# M606X.net
KiCad netlist of a schematic drawn in EAGLE
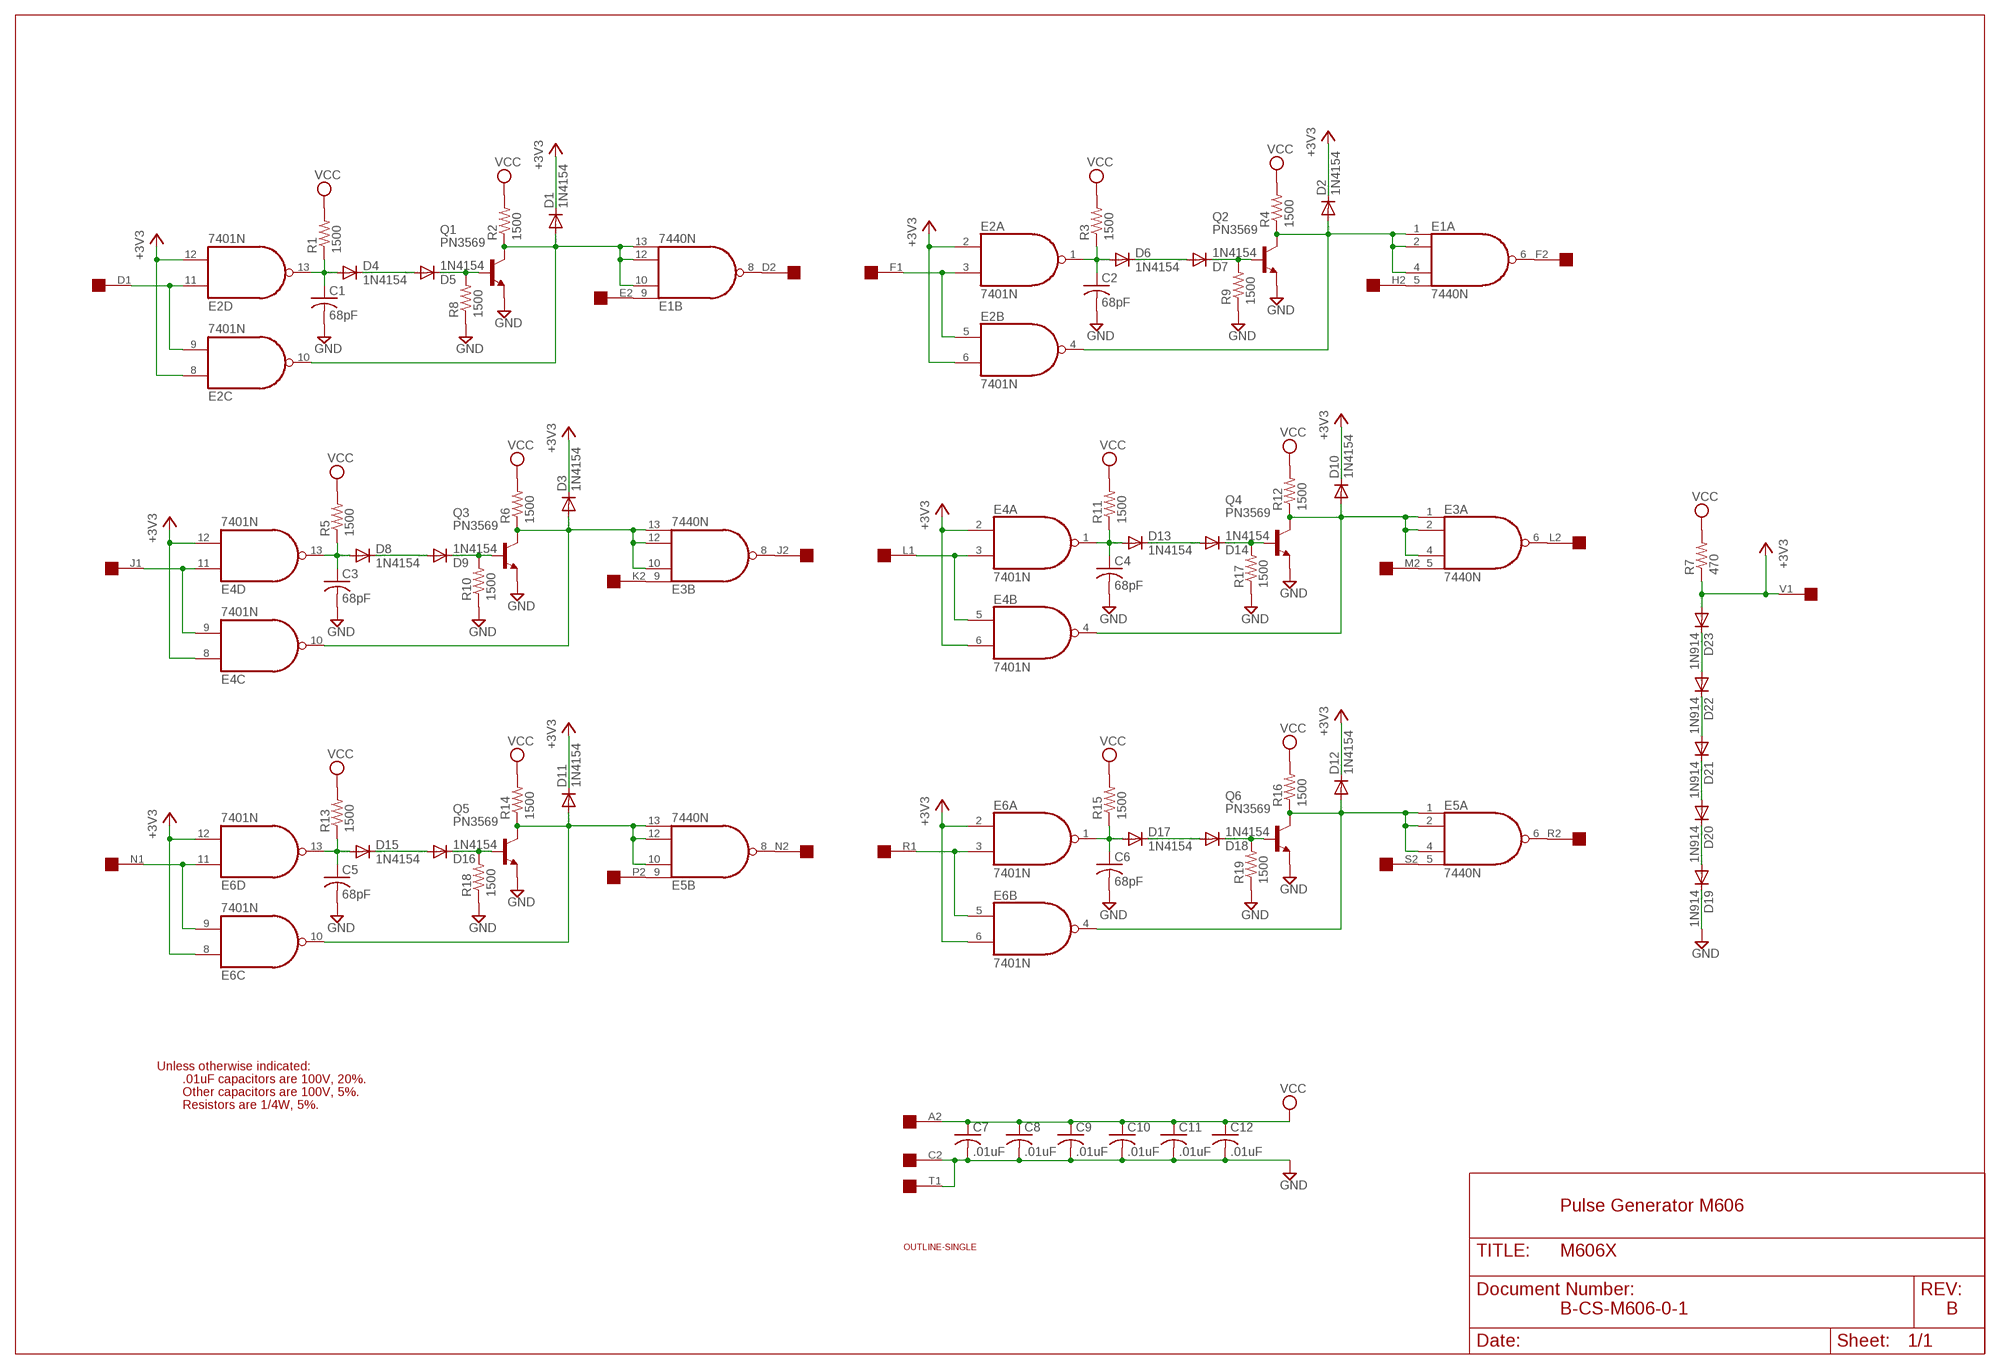
[diagram p0: schematic, sheet 1]

(export (version "E")
  (design (tool "Eeschema 10.0.6"))
  (components
    (comp (ref "C1")
      (value "68pF")
      (footprint "eagle-import:C075-032X103")
      (libsource (lib "eagle-import") (part "C-US075-032X103"))
    )
    (comp (ref "C2")
      (value "68pF")
      (footprint "eagle-import:C075-032X103")
      (libsource (lib "eagle-import") (part "C-US075-032X103"))
    )
    (comp (ref "C3")
      (value "68pF")
      (footprint "eagle-import:C075-032X103")
      (libsource (lib "eagle-import") (part "C-US075-032X103"))
    )
    (comp (ref "C4")
      (value "68pF")
      (footprint "eagle-import:C075-032X103")
      (libsource (lib "eagle-import") (part "C-US075-032X103"))
    )
    (comp (ref "C5")
      (value "68pF")
      (footprint "eagle-import:C075-032X103")
      (libsource (lib "eagle-import") (part "C-US075-032X103"))
    )
    (comp (ref "C6")
      (value "68pF")
      (footprint "eagle-import:C075-032X103")
      (libsource (lib "eagle-import") (part "C-US075-032X103"))
    )
    (comp (ref "C7")
      (value ".01uF")
      (footprint "eagle-import:C050-025X075")
      (libsource (lib "eagle-import") (part "C-US050-025X075"))
    )
    (comp (ref "C8")
      (value ".01uF")
      (footprint "eagle-import:C050-025X075")
      (libsource (lib "eagle-import") (part "C-US050-025X075"))
    )
    (comp (ref "C9")
      (value ".01uF")
      (footprint "eagle-import:C050-025X075")
      (libsource (lib "eagle-import") (part "C-US050-025X075"))
    )
    (comp (ref "C10")
      (value ".01uF")
      (footprint "eagle-import:C050-025X075")
      (libsource (lib "eagle-import") (part "C-US050-025X075"))
    )
    (comp (ref "C11")
      (value ".01uF")
      (footprint "eagle-import:C050-025X075")
      (libsource (lib "eagle-import") (part "C-US050-025X075"))
    )
    (comp (ref "C12")
      (value ".01uF")
      (footprint "eagle-import:C050-025X075")
      (libsource (lib "eagle-import") (part "C-US050-025X075"))
    )
    (comp (ref "D1")
      (value "1N4154")
      (footprint "eagle-import:DO35-10")
      (libsource (lib "eagle-import") (part "1N4148DO35-10"))
    )
    (comp (ref "D2")
      (value "1N4154")
      (footprint "eagle-import:DO35-10")
      (libsource (lib "eagle-import") (part "1N4148DO35-10"))
    )
    (comp (ref "D3")
      (value "1N4154")
      (footprint "eagle-import:DO35-10")
      (libsource (lib "eagle-import") (part "1N4148DO35-10"))
    )
    (comp (ref "D4")
      (value "1N4154")
      (footprint "eagle-import:DO35-10")
      (libsource (lib "eagle-import") (part "1N4148DO35-10"))
    )
    (comp (ref "D5")
      (value "1N4154")
      (footprint "eagle-import:DO35-10")
      (libsource (lib "eagle-import") (part "1N4148DO35-10"))
    )
    (comp (ref "D6")
      (value "1N4154")
      (footprint "eagle-import:DO35-10")
      (libsource (lib "eagle-import") (part "1N4148DO35-10"))
    )
    (comp (ref "D7")
      (value "1N4154")
      (footprint "eagle-import:DO35-10")
      (libsource (lib "eagle-import") (part "1N4148DO35-10"))
    )
    (comp (ref "D8")
      (value "1N4154")
      (footprint "eagle-import:DO35-10")
      (libsource (lib "eagle-import") (part "1N4148DO35-10"))
    )
    (comp (ref "D9")
      (value "1N4154")
      (footprint "eagle-import:DO35-10")
      (libsource (lib "eagle-import") (part "1N4148DO35-10"))
    )
    (comp (ref "D10")
      (value "1N4154")
      (footprint "eagle-import:DO35-10")
      (libsource (lib "eagle-import") (part "1N4148DO35-10"))
    )
    (comp (ref "D11")
      (value "1N4154")
      (footprint "eagle-import:DO35-10")
      (libsource (lib "eagle-import") (part "1N4148DO35-10"))
    )
    (comp (ref "D12")
      (value "1N4154")
      (footprint "eagle-import:DO35-10")
      (libsource (lib "eagle-import") (part "1N4148DO35-10"))
    )
    (comp (ref "D13")
      (value "1N4154")
      (footprint "eagle-import:DO35-10")
      (libsource (lib "eagle-import") (part "1N4148DO35-10"))
    )
    (comp (ref "D14")
      (value "1N4154")
      (footprint "eagle-import:DO35-10")
      (libsource (lib "eagle-import") (part "1N4148DO35-10"))
    )
    (comp (ref "D15")
      (value "1N4154")
      (footprint "eagle-import:DO35-10")
      (libsource (lib "eagle-import") (part "1N4148DO35-10"))
    )
    (comp (ref "D16")
      (value "1N4154")
      (footprint "eagle-import:DO35-10")
      (libsource (lib "eagle-import") (part "1N4148DO35-10"))
    )
    (comp (ref "D17")
      (value "1N4154")
      (footprint "eagle-import:DO35-10")
      (libsource (lib "eagle-import") (part "1N4148DO35-10"))
    )
    (comp (ref "D18")
      (value "1N4154")
      (footprint "eagle-import:DO35-10")
      (libsource (lib "eagle-import") (part "1N4148DO35-10"))
    )
    (comp (ref "D19")
      (value "1N914")
      (footprint "eagle-import:DO35-10")
      (libsource (lib "eagle-import") (part "1N4148DO35-10"))
    )
    (comp (ref "D20")
      (value "1N914")
      (footprint "eagle-import:DO35-10")
      (libsource (lib "eagle-import") (part "1N4148DO35-10"))
    )
    (comp (ref "D21")
      (value "1N914")
      (footprint "eagle-import:DO35-10")
      (libsource (lib "eagle-import") (part "1N4148DO35-10"))
    )
    (comp (ref "D22")
      (value "1N914")
      (footprint "eagle-import:DO35-10")
      (libsource (lib "eagle-import") (part "1N4148DO35-10"))
    )
    (comp (ref "D23")
      (value "1N914")
      (footprint "eagle-import:DO35-10")
      (libsource (lib "eagle-import") (part "1N4148DO35-10"))
    )
    (comp (ref "E1")
      (value "7440N")
      (footprint "eagle-import:DIL14")
      (libsource (lib "eagle-import") (part "7420NS"))
    )
    (comp (ref "E2")
      (value "7401N")
      (footprint "eagle-import:DIL14")
      (libsource (lib "eagle-import") (part "7401NLS"))
    )
    (comp (ref "E3")
      (value "7440N")
      (footprint "eagle-import:DIL14")
      (libsource (lib "eagle-import") (part "7420NS"))
    )
    (comp (ref "E4")
      (value "7401N")
      (footprint "eagle-import:DIL14")
      (libsource (lib "eagle-import") (part "7401NLS"))
    )
    (comp (ref "E5")
      (value "7440N")
      (footprint "eagle-import:DIL14")
      (libsource (lib "eagle-import") (part "7420NS"))
    )
    (comp (ref "E6")
      (value "7401N")
      (footprint "eagle-import:DIL14")
      (libsource (lib "eagle-import") (part "7401NLS"))
    )
    (comp (ref "Q1")
      (value "PN3569")
      (footprint "eagle-import:TO39")
      (libsource (lib "eagle-import") (part "2N3019"))
    )
    (comp (ref "Q2")
      (value "PN3569")
      (footprint "eagle-import:TO39")
      (libsource (lib "eagle-import") (part "2N3019"))
    )
    (comp (ref "Q3")
      (value "PN3569")
      (footprint "eagle-import:TO39")
      (libsource (lib "eagle-import") (part "2N3019"))
    )
    (comp (ref "Q4")
      (value "PN3569")
      (footprint "eagle-import:TO39")
      (libsource (lib "eagle-import") (part "2N3019"))
    )
    (comp (ref "Q5")
      (value "PN3569")
      (footprint "eagle-import:TO39")
      (libsource (lib "eagle-import") (part "2N3019"))
    )
    (comp (ref "Q6")
      (value "PN3569")
      (footprint "eagle-import:TO39")
      (libsource (lib "eagle-import") (part "2N3019"))
    )
    (comp (ref "R1")
      (value "1500")
      (footprint "eagle-import:0207_10")
      (libsource (lib "eagle-import") (part "R-US_0207/10"))
    )
    (comp (ref "R2")
      (value "1500")
      (footprint "eagle-import:0207_10")
      (libsource (lib "eagle-import") (part "R-US_0207/10"))
    )
    (comp (ref "R3")
      (value "1500")
      (footprint "eagle-import:0207_10")
      (libsource (lib "eagle-import") (part "R-US_0207/10"))
    )
    (comp (ref "R4")
      (value "1500")
      (footprint "eagle-import:0207_10")
      (libsource (lib "eagle-import") (part "R-US_0207/10"))
    )
    (comp (ref "R5")
      (value "1500")
      (footprint "eagle-import:0207_10")
      (libsource (lib "eagle-import") (part "R-US_0207/10"))
    )
    (comp (ref "R6")
      (value "1500")
      (footprint "eagle-import:0207_10")
      (libsource (lib "eagle-import") (part "R-US_0207/10"))
    )
    (comp (ref "R7")
      (value "470")
      (footprint "eagle-import:0207_10")
      (libsource (lib "eagle-import") (part "R-US_0207/10"))
    )
    (comp (ref "R8")
      (value "1500")
      (footprint "eagle-import:0207_10")
      (libsource (lib "eagle-import") (part "R-US_0207/10"))
    )
    (comp (ref "R9")
      (value "1500")
      (footprint "eagle-import:0207_10")
      (libsource (lib "eagle-import") (part "R-US_0207/10"))
    )
    (comp (ref "R10")
      (value "1500")
      (footprint "eagle-import:0207_10")
      (libsource (lib "eagle-import") (part "R-US_0207/10"))
    )
    (comp (ref "R11")
      (value "1500")
      (footprint "eagle-import:0207_10")
      (libsource (lib "eagle-import") (part "R-US_0207/10"))
    )
    (comp (ref "R12")
      (value "1500")
      (footprint "eagle-import:0207_10")
      (libsource (lib "eagle-import") (part "R-US_0207/10"))
    )
    (comp (ref "R13")
      (value "1500")
      (footprint "eagle-import:0207_10")
      (libsource (lib "eagle-import") (part "R-US_0207/10"))
    )
    (comp (ref "R14")
      (value "1500")
      (footprint "eagle-import:0207_10")
      (libsource (lib "eagle-import") (part "R-US_0207/10"))
    )
    (comp (ref "R15")
      (value "1500")
      (footprint "eagle-import:0207_10")
      (libsource (lib "eagle-import") (part "R-US_0207/10"))
    )
    (comp (ref "R16")
      (value "1500")
      (footprint "eagle-import:0207_10")
      (libsource (lib "eagle-import") (part "R-US_0207/10"))
    )
    (comp (ref "R17")
      (value "1500")
      (footprint "eagle-import:0207_10")
      (libsource (lib "eagle-import") (part "R-US_0207/10"))
    )
    (comp (ref "R18")
      (value "1500")
      (footprint "eagle-import:0207_10")
      (libsource (lib "eagle-import") (part "R-US_0207/10"))
    )
    (comp (ref "R19")
      (value "1500")
      (footprint "eagle-import:0207_10")
      (libsource (lib "eagle-import") (part "R-US_0207/10"))
    )
    (comp (ref "U$2")
      (value "SINGLE")
      (footprint "eagle-import:EDGE-CON2")
      (libsource (lib "eagle-import") (part "SINGLE"))
    )
    (comp (ref "U$4")
      (value "OUTLINE-SINGLE")
      (footprint "eagle-import:SINGLE")
      (libsource (lib "eagle-import") (part "OUTLINE-SINGLE"))
    )
  )
  (nets
    (net (code "1") (name "+3V3") (class "Default")
      (node (ref "D1") (pin "C") (pinfunction "C_C") (pintype "passive"))
      (node (ref "D10") (pin "C") (pinfunction "C_C") (pintype "passive"))
      (node (ref "D11") (pin "C") (pinfunction "C_C") (pintype "passive"))
      (node (ref "D12") (pin "C") (pinfunction "C_C") (pintype "passive"))
      (node (ref "D2") (pin "C") (pinfunction "C_C") (pintype "passive"))
      (node (ref "D23") (pin "A") (pinfunction "A_A") (pintype "passive"))
      (node (ref "D3") (pin "C") (pinfunction "C_C") (pintype "passive"))
      (node (ref "E2") (pin "12") (pinfunction "I1_12") (pintype "input"))
      (node (ref "E2") (pin "2") (pinfunction "I0_2") (pintype "input"))
      (node (ref "E2") (pin "6") (pinfunction "I1_6") (pintype "input"))
      (node (ref "E2") (pin "8") (pinfunction "I0_8") (pintype "input"))
      (node (ref "E4") (pin "12") (pinfunction "I1_12") (pintype "input"))
      (node (ref "E4") (pin "2") (pinfunction "I0_2") (pintype "input"))
      (node (ref "E4") (pin "6") (pinfunction "I1_6") (pintype "input"))
      (node (ref "E4") (pin "8") (pinfunction "I0_8") (pintype "input"))
      (node (ref "E6") (pin "12") (pinfunction "I1_12") (pintype "input"))
      (node (ref "E6") (pin "2") (pinfunction "I0_2") (pintype "input"))
      (node (ref "E6") (pin "6") (pinfunction "I1_6") (pintype "input"))
      (node (ref "E6") (pin "8") (pinfunction "I0_8") (pintype "input"))
      (node (ref "R7") (pin "1") (pinfunction "1_1") (pintype "passive"))
      (node (ref "U$2") (pin "V1") (pinfunction "1_V1") (pintype "bidirectional"))
    )
    (net (code "2") (name "GND") (class "Default")
      (node (ref "C1") (pin "2") (pinfunction "2_2") (pintype "passive"))
      (node (ref "C10") (pin "2") (pinfunction "2_2") (pintype "passive"))
      (node (ref "C11") (pin "2") (pinfunction "2_2") (pintype "passive"))
      (node (ref "C12") (pin "2") (pinfunction "2_2") (pintype "passive"))
      (node (ref "C2") (pin "2") (pinfunction "2_2") (pintype "passive"))
      (node (ref "C3") (pin "2") (pinfunction "2_2") (pintype "passive"))
      (node (ref "C4") (pin "2") (pinfunction "2_2") (pintype "passive"))
      (node (ref "C5") (pin "2") (pinfunction "2_2") (pintype "passive"))
      (node (ref "C6") (pin "2") (pinfunction "2_2") (pintype "passive"))
      (node (ref "C7") (pin "2") (pinfunction "2_2") (pintype "passive"))
      (node (ref "C8") (pin "2") (pinfunction "2_2") (pintype "passive"))
      (node (ref "C9") (pin "2") (pinfunction "2_2") (pintype "passive"))
      (node (ref "D19") (pin "C") (pinfunction "C_C") (pintype "passive"))
      (node (ref "Q1") (pin "1") (pinfunction "E_1") (pintype "passive"))
      (node (ref "Q2") (pin "1") (pinfunction "E_1") (pintype "passive"))
      (node (ref "Q3") (pin "1") (pinfunction "E_1") (pintype "passive"))
      (node (ref "Q4") (pin "1") (pinfunction "E_1") (pintype "passive"))
      (node (ref "Q5") (pin "1") (pinfunction "E_1") (pintype "passive"))
      (node (ref "Q6") (pin "1") (pinfunction "E_1") (pintype "passive"))
      (node (ref "R10") (pin "1") (pinfunction "1_1") (pintype "passive"))
      (node (ref "R17") (pin "1") (pinfunction "1_1") (pintype "passive"))
      (node (ref "R18") (pin "1") (pinfunction "1_1") (pintype "passive"))
      (node (ref "R19") (pin "1") (pinfunction "1_1") (pintype "passive"))
      (node (ref "R8") (pin "1") (pinfunction "1_1") (pintype "passive"))
      (node (ref "R9") (pin "1") (pinfunction "1_1") (pintype "passive"))
      (node (ref "U$2") (pin "C2") (pinfunction "1_C2") (pintype "bidirectional"))
      (node (ref "U$2") (pin "T1") (pinfunction "1_T1") (pintype "bidirectional"))
    )
    (net (code "3") (name "Net-(D4-PadC)") (class "Default")
      (node (ref "D4") (pin "C") (pinfunction "C_C") (pintype "passive"))
      (node (ref "D5") (pin "A") (pinfunction "A_A") (pintype "passive"))
    )
    (net (code "4") (name "Net-(D6-PadC)") (class "Default")
      (node (ref "D6") (pin "C") (pinfunction "C_C") (pintype "passive"))
      (node (ref "D7") (pin "A") (pinfunction "A_A") (pintype "passive"))
    )
    (net (code "5") (name "Net-(D8-PadC)") (class "Default")
      (node (ref "D8") (pin "C") (pinfunction "C_C") (pintype "passive"))
      (node (ref "D9") (pin "A") (pinfunction "A_A") (pintype "passive"))
    )
    (net (code "6") (name "Net-(D13-PadC)") (class "Default")
      (node (ref "D13") (pin "C") (pinfunction "C_C") (pintype "passive"))
      (node (ref "D14") (pin "A") (pinfunction "A_A") (pintype "passive"))
    )
    (net (code "7") (name "Net-(D15-PadC)") (class "Default")
      (node (ref "D15") (pin "C") (pinfunction "C_C") (pintype "passive"))
      (node (ref "D16") (pin "A") (pinfunction "A_A") (pintype "passive"))
    )
    (net (code "8") (name "Net-(D17-PadC)") (class "Default")
      (node (ref "D17") (pin "C") (pinfunction "C_C") (pintype "passive"))
      (node (ref "D18") (pin "A") (pinfunction "A_A") (pintype "passive"))
    )
    (net (code "9") (name "Net-(D19-PadA)") (class "Default")
      (node (ref "D19") (pin "A") (pinfunction "A_A") (pintype "passive"))
      (node (ref "D20") (pin "C") (pinfunction "C_C") (pintype "passive"))
    )
    (net (code "10") (name "Net-(D20-PadA)") (class "Default")
      (node (ref "D20") (pin "A") (pinfunction "A_A") (pintype "passive"))
      (node (ref "D21") (pin "C") (pinfunction "C_C") (pintype "passive"))
    )
    (net (code "11") (name "Net-(D21-PadA)") (class "Default")
      (node (ref "D21") (pin "A") (pinfunction "A_A") (pintype "passive"))
      (node (ref "D22") (pin "C") (pinfunction "C_C") (pintype "passive"))
    )
    (net (code "12") (name "Net-(D22-PadA)") (class "Default")
      (node (ref "D22") (pin "A") (pinfunction "A_A") (pintype "passive"))
      (node (ref "D23") (pin "C") (pinfunction "C_C") (pintype "passive"))
    )
    (net (code "13") (name "Net-(E1A-I0)") (class "Default")
      (node (ref "D2") (pin "A") (pinfunction "A_A") (pintype "passive"))
      (node (ref "E1") (pin "1") (pinfunction "I0_1") (pintype "input"))
      (node (ref "E1") (pin "2") (pinfunction "I1_2") (pintype "input"))
      (node (ref "E1") (pin "4") (pinfunction "I2_4") (pintype "input"))
      (node (ref "E2") (pin "4") (pinfunction "O_4") (pintype "open_collector"))
      (node (ref "Q2") (pin "3") (pinfunction "C_3") (pintype "passive"))
      (node (ref "R4") (pin "1") (pinfunction "1_1") (pintype "passive"))
    )
    (net (code "14") (name "Net-(E1A-I3)") (class "Default")
      (node (ref "E1") (pin "5") (pinfunction "I3_5") (pintype "input"))
      (node (ref "U$2") (pin "H2") (pinfunction "1_H2") (pintype "bidirectional"))
    )
    (net (code "15") (name "Net-(E1A-O)") (class "Default")
      (node (ref "E1") (pin "6") (pinfunction "O_6") (pintype "output"))
      (node (ref "U$2") (pin "F2") (pinfunction "1_F2") (pintype "bidirectional"))
    )
    (net (code "16") (name "Net-(E1B-I0)") (class "Default")
      (node (ref "E1") (pin "9") (pinfunction "I0_9") (pintype "input"))
      (node (ref "U$2") (pin "E2") (pinfunction "1_E2") (pintype "bidirectional"))
    )
    (net (code "17") (name "Net-(E1B-I1)") (class "Default")
      (node (ref "D1") (pin "A") (pinfunction "A_A") (pintype "passive"))
      (node (ref "E1") (pin "10") (pinfunction "I1_10") (pintype "input"))
      (node (ref "E1") (pin "12") (pinfunction "I2_12") (pintype "input"))
      (node (ref "E1") (pin "13") (pinfunction "I3_13") (pintype "input"))
      (node (ref "E2") (pin "10") (pinfunction "O_10") (pintype "open_collector"))
      (node (ref "Q1") (pin "3") (pinfunction "C_3") (pintype "passive"))
      (node (ref "R2") (pin "1") (pinfunction "1_1") (pintype "passive"))
    )
    (net (code "18") (name "Net-(E1B-O)") (class "Default")
      (node (ref "E1") (pin "8") (pinfunction "O_8") (pintype "output"))
      (node (ref "U$2") (pin "D2") (pinfunction "1_D2") (pintype "bidirectional"))
    )
    (net (code "19") (name "Net-(E2A-I1)") (class "Default")
      (node (ref "E2") (pin "3") (pinfunction "I1_3") (pintype "input"))
      (node (ref "E2") (pin "5") (pinfunction "I0_5") (pintype "input"))
      (node (ref "U$2") (pin "F1") (pinfunction "1_F1") (pintype "bidirectional"))
    )
    (net (code "20") (name "Net-(E2A-O)") (class "Default")
      (node (ref "C2") (pin "1") (pinfunction "1_1") (pintype "passive"))
      (node (ref "D6") (pin "A") (pinfunction "A_A") (pintype "passive"))
      (node (ref "E2") (pin "1") (pinfunction "O_1") (pintype "open_collector"))
      (node (ref "R3") (pin "1") (pinfunction "1_1") (pintype "passive"))
    )
    (net (code "21") (name "Net-(E2C-I1)") (class "Default")
      (node (ref "E2") (pin "11") (pinfunction "I0_11") (pintype "input"))
      (node (ref "E2") (pin "9") (pinfunction "I1_9") (pintype "input"))
      (node (ref "U$2") (pin "D1") (pinfunction "1_D1") (pintype "bidirectional"))
    )
    (net (code "22") (name "Net-(E2D-O)") (class "Default")
      (node (ref "C1") (pin "1") (pinfunction "1_1") (pintype "passive"))
      (node (ref "D4") (pin "A") (pinfunction "A_A") (pintype "passive"))
      (node (ref "E2") (pin "13") (pinfunction "O_13") (pintype "open_collector"))
      (node (ref "R1") (pin "1") (pinfunction "1_1") (pintype "passive"))
    )
    (net (code "23") (name "Net-(E3A-I0)") (class "Default")
      (node (ref "D10") (pin "A") (pinfunction "A_A") (pintype "passive"))
      (node (ref "E3") (pin "1") (pinfunction "I0_1") (pintype "input"))
      (node (ref "E3") (pin "2") (pinfunction "I1_2") (pintype "input"))
      (node (ref "E3") (pin "4") (pinfunction "I2_4") (pintype "input"))
      (node (ref "E4") (pin "4") (pinfunction "O_4") (pintype "open_collector"))
      (node (ref "Q4") (pin "3") (pinfunction "C_3") (pintype "passive"))
      (node (ref "R12") (pin "1") (pinfunction "1_1") (pintype "passive"))
    )
    (net (code "24") (name "Net-(E3A-I3)") (class "Default")
      (node (ref "E3") (pin "5") (pinfunction "I3_5") (pintype "input"))
      (node (ref "U$2") (pin "M2") (pinfunction "1_M2") (pintype "bidirectional"))
    )
    (net (code "25") (name "Net-(E3A-O)") (class "Default")
      (node (ref "E3") (pin "6") (pinfunction "O_6") (pintype "output"))
      (node (ref "U$2") (pin "L2") (pinfunction "1_L2") (pintype "bidirectional"))
    )
    (net (code "26") (name "Net-(E3B-I0)") (class "Default")
      (node (ref "E3") (pin "9") (pinfunction "I0_9") (pintype "input"))
      (node (ref "U$2") (pin "K2") (pinfunction "1_K2") (pintype "bidirectional"))
    )
    (net (code "27") (name "Net-(E3B-I1)") (class "Default")
      (node (ref "D3") (pin "A") (pinfunction "A_A") (pintype "passive"))
      (node (ref "E3") (pin "10") (pinfunction "I1_10") (pintype "input"))
      (node (ref "E3") (pin "12") (pinfunction "I2_12") (pintype "input"))
      (node (ref "E3") (pin "13") (pinfunction "I3_13") (pintype "input"))
      (node (ref "E4") (pin "10") (pinfunction "O_10") (pintype "open_collector"))
      (node (ref "Q3") (pin "3") (pinfunction "C_3") (pintype "passive"))
      (node (ref "R6") (pin "1") (pinfunction "1_1") (pintype "passive"))
    )
    (net (code "28") (name "Net-(E3B-O)") (class "Default")
      (node (ref "E3") (pin "8") (pinfunction "O_8") (pintype "output"))
      (node (ref "U$2") (pin "J2") (pinfunction "1_J2") (pintype "bidirectional"))
    )
    (net (code "29") (name "Net-(E4A-I1)") (class "Default")
      (node (ref "E4") (pin "3") (pinfunction "I1_3") (pintype "input"))
      (node (ref "E4") (pin "5") (pinfunction "I0_5") (pintype "input"))
      (node (ref "U$2") (pin "L1") (pinfunction "1_L1") (pintype "bidirectional"))
    )
    (net (code "30") (name "Net-(E4A-O)") (class "Default")
      (node (ref "C4") (pin "1") (pinfunction "1_1") (pintype "passive"))
      (node (ref "D13") (pin "A") (pinfunction "A_A") (pintype "passive"))
      (node (ref "E4") (pin "1") (pinfunction "O_1") (pintype "open_collector"))
      (node (ref "R11") (pin "1") (pinfunction "1_1") (pintype "passive"))
    )
    (net (code "31") (name "Net-(E4C-I1)") (class "Default")
      (node (ref "E4") (pin "11") (pinfunction "I0_11") (pintype "input"))
      (node (ref "E4") (pin "9") (pinfunction "I1_9") (pintype "input"))
      (node (ref "U$2") (pin "J1") (pinfunction "1_J1") (pintype "bidirectional"))
    )
    (net (code "32") (name "Net-(E4D-O)") (class "Default")
      (node (ref "C3") (pin "1") (pinfunction "1_1") (pintype "passive"))
      (node (ref "D8") (pin "A") (pinfunction "A_A") (pintype "passive"))
      (node (ref "E4") (pin "13") (pinfunction "O_13") (pintype "open_collector"))
      (node (ref "R5") (pin "1") (pinfunction "1_1") (pintype "passive"))
    )
    (net (code "33") (name "Net-(E5A-I0)") (class "Default")
      (node (ref "D12") (pin "A") (pinfunction "A_A") (pintype "passive"))
      (node (ref "E5") (pin "1") (pinfunction "I0_1") (pintype "input"))
      (node (ref "E5") (pin "2") (pinfunction "I1_2") (pintype "input"))
      (node (ref "E5") (pin "4") (pinfunction "I2_4") (pintype "input"))
      (node (ref "E6") (pin "4") (pinfunction "O_4") (pintype "open_collector"))
      (node (ref "Q6") (pin "3") (pinfunction "C_3") (pintype "passive"))
      (node (ref "R16") (pin "1") (pinfunction "1_1") (pintype "passive"))
    )
    (net (code "34") (name "Net-(E5A-I3)") (class "Default")
      (node (ref "E5") (pin "5") (pinfunction "I3_5") (pintype "input"))
      (node (ref "U$2") (pin "S2") (pinfunction "1_S2") (pintype "bidirectional"))
    )
    (net (code "35") (name "Net-(E5A-O)") (class "Default")
      (node (ref "E5") (pin "6") (pinfunction "O_6") (pintype "output"))
      (node (ref "U$2") (pin "R2") (pinfunction "1_R2") (pintype "bidirectional"))
    )
    (net (code "36") (name "Net-(E5B-I0)") (class "Default")
      (node (ref "E5") (pin "9") (pinfunction "I0_9") (pintype "input"))
      (node (ref "U$2") (pin "P2") (pinfunction "1_P2") (pintype "bidirectional"))
    )
    (net (code "37") (name "Net-(E5B-I1)") (class "Default")
      (node (ref "D11") (pin "A") (pinfunction "A_A") (pintype "passive"))
      (node (ref "E5") (pin "10") (pinfunction "I1_10") (pintype "input"))
      (node (ref "E5") (pin "12") (pinfunction "I2_12") (pintype "input"))
      (node (ref "E5") (pin "13") (pinfunction "I3_13") (pintype "input"))
      (node (ref "E6") (pin "10") (pinfunction "O_10") (pintype "open_collector"))
      (node (ref "Q5") (pin "3") (pinfunction "C_3") (pintype "passive"))
      (node (ref "R14") (pin "1") (pinfunction "1_1") (pintype "passive"))
    )
    (net (code "38") (name "Net-(E5B-O)") (class "Default")
      (node (ref "E5") (pin "8") (pinfunction "O_8") (pintype "output"))
      (node (ref "U$2") (pin "N2") (pinfunction "1_N2") (pintype "bidirectional"))
    )
    (net (code "39") (name "Net-(E6A-I1)") (class "Default")
      (node (ref "E6") (pin "3") (pinfunction "I1_3") (pintype "input"))
      (node (ref "E6") (pin "5") (pinfunction "I0_5") (pintype "input"))
      (node (ref "U$2") (pin "R1") (pinfunction "1_R1") (pintype "bidirectional"))
    )
    (net (code "40") (name "Net-(E6A-O)") (class "Default")
      (node (ref "C6") (pin "1") (pinfunction "1_1") (pintype "passive"))
      (node (ref "D17") (pin "A") (pinfunction "A_A") (pintype "passive"))
      (node (ref "E6") (pin "1") (pinfunction "O_1") (pintype "open_collector"))
      (node (ref "R15") (pin "1") (pinfunction "1_1") (pintype "passive"))
    )
    (net (code "41") (name "Net-(E6C-I1)") (class "Default")
      (node (ref "E6") (pin "11") (pinfunction "I0_11") (pintype "input"))
      (node (ref "E6") (pin "9") (pinfunction "I1_9") (pintype "input"))
      (node (ref "U$2") (pin "N1") (pinfunction "1_N1") (pintype "bidirectional"))
    )
    (net (code "42") (name "Net-(E6D-O)") (class "Default")
      (node (ref "C5") (pin "1") (pinfunction "1_1") (pintype "passive"))
      (node (ref "D15") (pin "A") (pinfunction "A_A") (pintype "passive"))
      (node (ref "E6") (pin "13") (pinfunction "O_13") (pintype "open_collector"))
      (node (ref "R13") (pin "1") (pinfunction "1_1") (pintype "passive"))
    )
    (net (code "43") (name "Net-(Q1-B)") (class "Default")
      (node (ref "D5") (pin "C") (pinfunction "C_C") (pintype "passive"))
      (node (ref "Q1") (pin "2") (pinfunction "B_2") (pintype "passive"))
      (node (ref "R8") (pin "2") (pinfunction "2_2") (pintype "passive"))
    )
    (net (code "44") (name "Net-(Q2-B)") (class "Default")
      (node (ref "D7") (pin "C") (pinfunction "C_C") (pintype "passive"))
      (node (ref "Q2") (pin "2") (pinfunction "B_2") (pintype "passive"))
      (node (ref "R9") (pin "2") (pinfunction "2_2") (pintype "passive"))
    )
    (net (code "45") (name "Net-(Q3-B)") (class "Default")
      (node (ref "D9") (pin "C") (pinfunction "C_C") (pintype "passive"))
      (node (ref "Q3") (pin "2") (pinfunction "B_2") (pintype "passive"))
      (node (ref "R10") (pin "2") (pinfunction "2_2") (pintype "passive"))
    )
    (net (code "46") (name "Net-(Q4-B)") (class "Default")
      (node (ref "D14") (pin "C") (pinfunction "C_C") (pintype "passive"))
      (node (ref "Q4") (pin "2") (pinfunction "B_2") (pintype "passive"))
      (node (ref "R17") (pin "2") (pinfunction "2_2") (pintype "passive"))
    )
    (net (code "47") (name "Net-(Q5-B)") (class "Default")
      (node (ref "D16") (pin "C") (pinfunction "C_C") (pintype "passive"))
      (node (ref "Q5") (pin "2") (pinfunction "B_2") (pintype "passive"))
      (node (ref "R18") (pin "2") (pinfunction "2_2") (pintype "passive"))
    )
    (net (code "48") (name "Net-(Q6-B)") (class "Default")
      (node (ref "D18") (pin "C") (pinfunction "C_C") (pintype "passive"))
      (node (ref "Q6") (pin "2") (pinfunction "B_2") (pintype "passive"))
      (node (ref "R19") (pin "2") (pinfunction "2_2") (pintype "passive"))
    )
    (net (code "49") (name "VCC") (class "Default")
      (node (ref "C10") (pin "1") (pinfunction "1_1") (pintype "passive"))
      (node (ref "C11") (pin "1") (pinfunction "1_1") (pintype "passive"))
      (node (ref "C12") (pin "1") (pinfunction "1_1") (pintype "passive"))
      (node (ref "C7") (pin "1") (pinfunction "1_1") (pintype "passive"))
      (node (ref "C8") (pin "1") (pinfunction "1_1") (pintype "passive"))
      (node (ref "C9") (pin "1") (pinfunction "1_1") (pintype "passive"))
      (node (ref "R1") (pin "2") (pinfunction "2_2") (pintype "passive"))
      (node (ref "R11") (pin "2") (pinfunction "2_2") (pintype "passive"))
      (node (ref "R12") (pin "2") (pinfunction "2_2") (pintype "passive"))
      (node (ref "R13") (pin "2") (pinfunction "2_2") (pintype "passive"))
      (node (ref "R14") (pin "2") (pinfunction "2_2") (pintype "passive"))
      (node (ref "R15") (pin "2") (pinfunction "2_2") (pintype "passive"))
      (node (ref "R16") (pin "2") (pinfunction "2_2") (pintype "passive"))
      (node (ref "R2") (pin "2") (pinfunction "2_2") (pintype "passive"))
      (node (ref "R3") (pin "2") (pinfunction "2_2") (pintype "passive"))
      (node (ref "R4") (pin "2") (pinfunction "2_2") (pintype "passive"))
      (node (ref "R5") (pin "2") (pinfunction "2_2") (pintype "passive"))
      (node (ref "R6") (pin "2") (pinfunction "2_2") (pintype "passive"))
      (node (ref "R7") (pin "2") (pinfunction "2_2") (pintype "passive"))
      (node (ref "U$2") (pin "A2") (pinfunction "1_A2") (pintype "bidirectional"))
    )
  )
)
